# Dash22_LEDS.net
KiCad netlist of a schematic drawn in Altium Designer
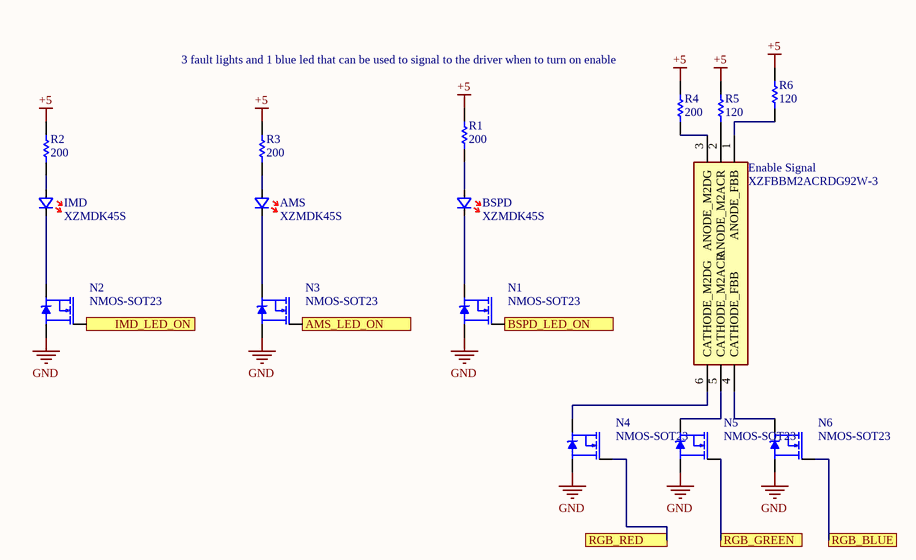
[diagram p0: Dash22_LEDS.SchDoc]

(export (version "E")
  (design (tool "Eeschema 10.0.6"))
  (components
    (comp (ref "AMS")
      (value "XZMDK45S")
      (footprint "LED_XZFBB45S")
      (fields (field (name "SOURCE") "ife19_Elec_Library.schlib"))
      (libsource (lib "Illini Formula Electric") (part "Symbol"))
    )
    (comp (ref "BSPD")
      (value "XZMDK45S")
      (footprint "LED_XZFBB45S")
      (fields (field (name "SOURCE") "ife19_Elec_Library.schlib"))
      (libsource (lib "Illini Formula Electric") (part "Symbol"))
    )
    (comp (ref "Enable Signal")
      (value "XZFBBM2ACRDG92W-3")
      (footprint "SamacSys:XZFBBM2ACRDG92W3")
      (description "LED")
      (libsource (lib "*") (part "XZFBBM2ACRDG92W-3"))
    )
    (comp (ref "IMD")
      (value "XZMDK45S")
      (footprint "LED_XZFBB45S")
      (fields (field (name "SOURCE") "ife19_Elec_Library.schlib"))
      (libsource (lib "Illini Formula Electric") (part "Symbol"))
    )
    (comp (ref "N1")
      (value "NMOS-SOT23")
      (footprint "SOT23")
      (fields (field (name "SOURCE") "ife19_Elec_Library.schlib"))
      (libsource (lib "Illini Formula Electric") (part "NMOS-SOT23"))
    )
    (comp (ref "N2")
      (value "NMOS-SOT23")
      (footprint "SOT23")
      (fields (field (name "SOURCE") "ife19_Elec_Library.schlib"))
      (libsource (lib "Illini Formula Electric") (part "NMOS-SOT23"))
    )
    (comp (ref "N3")
      (value "NMOS-SOT23")
      (footprint "SOT23")
      (fields (field (name "SOURCE") "ife19_Elec_Library.schlib"))
      (libsource (lib "Illini Formula Electric") (part "NMOS-SOT23"))
    )
    (comp (ref "N4")
      (value "NMOS-SOT23")
      (footprint "SOT23")
      (fields (field (name "SOURCE") "ife19_Elec_Library.schlib"))
      (libsource (lib "Illini Formula Electric") (part "NMOS-SOT23"))
    )
    (comp (ref "N5")
      (value "NMOS-SOT23")
      (footprint "SOT23")
      (fields (field (name "SOURCE") "ife19_Elec_Library.schlib"))
      (libsource (lib "Illini Formula Electric") (part "NMOS-SOT23"))
    )
    (comp (ref "N6")
      (value "NMOS-SOT23")
      (footprint "SOT23")
      (fields (field (name "SOURCE") "ife19_Elec_Library.schlib"))
      (libsource (lib "Illini Formula Electric") (part "NMOS-SOT23"))
    )
    (comp (ref "R1")
      (value "200")
      (footprint "RESC1608X55X25ML10T15")
      (description "Chip Resistor, 0 Ohm, 0.1 W, -55 to 155 degC, 0603 (1608 Metric)")
      (libsource (lib "") (part "Symbol_1"))
    )
    (comp (ref "R2")
      (value "200")
      (footprint "RESC1608X55X25ML10T15")
      (description "Chip Resistor, 0 Ohm, 0.1 W, -55 to 155 degC, 0603 (1608 Metric)")
      (libsource (lib "") (part "Symbol_1"))
    )
    (comp (ref "R3")
      (value "200")
      (footprint "RESC1608X55X25ML10T15")
      (description "Chip Resistor, 0 Ohm, 0.1 W, -55 to 155 degC, 0603 (1608 Metric)")
      (libsource (lib "") (part "Symbol_1"))
    )
    (comp (ref "R4")
      (value "200")
      (footprint "RESC1608X55X25ML10T15")
      (description "Chip Resistor, 0 Ohm, 0.1 W, -55 to 155 degC, 0603 (1608 Metric)")
      (libsource (lib "") (part "Symbol_1"))
    )
    (comp (ref "R5")
      (value "120")
      (footprint "RESC1608X55X25ML10T15")
      (description "Chip Resistor, 0 Ohm, 0.1 W, -55 to 155 degC, 0603 (1608 Metric)")
      (libsource (lib "") (part "Symbol_1"))
    )
    (comp (ref "R6")
      (value "120")
      (footprint "RESC1608X55X25ML10T15")
      (description "Chip Resistor, 0 Ohm, 0.1 W, -55 to 155 degC, 0603 (1608 Metric)")
      (libsource (lib "") (part "Symbol_1"))
    )
  )
  (nets
    (net (code "1") (name "+5") (class "Default")
      (node (ref "R1") (pin "2") (pinfunction "2_2") (pintype "passive"))
      (node (ref "R2") (pin "2") (pinfunction "2_2") (pintype "passive"))
      (node (ref "R3") (pin "2") (pinfunction "2_2") (pintype "passive"))
      (node (ref "R4") (pin "2") (pinfunction "2_2") (pintype "passive"))
      (node (ref "R5") (pin "2") (pinfunction "2_2") (pintype "passive"))
      (node (ref "R6") (pin "2") (pinfunction "2_2") (pintype "passive"))
    )
    (net (code "2") (name "/AMS_LED_ON") (class "Default")
      (node (ref "N3") (pin "1") (pinfunction "G_1") (pintype "passive"))
    )
    (net (code "3") (name "/BSPD_LED_ON") (class "Default")
      (node (ref "N1") (pin "1") (pinfunction "G_1") (pintype "passive"))
    )
    (net (code "4") (name "/IMD_LED_ON") (class "Default")
      (node (ref "N2") (pin "1") (pinfunction "G_1") (pintype "passive"))
    )
    (net (code "5") (name "/RGB_BLUE") (class "Default")
      (node (ref "N6") (pin "1") (pinfunction "G_1") (pintype "passive"))
    )
    (net (code "6") (name "/RGB_GREEN") (class "Default")
      (node (ref "N5") (pin "1") (pinfunction "G_1") (pintype "passive"))
    )
    (net (code "7") (name "/RGB_RED") (class "Default")
      (node (ref "N4") (pin "1") (pinfunction "G_1") (pintype "passive"))
    )
    (net (code "8") (name "GND") (class "Default")
      (node (ref "N1") (pin "2") (pinfunction "S_2") (pintype "passive"))
      (node (ref "N2") (pin "2") (pinfunction "S_2") (pintype "passive"))
      (node (ref "N3") (pin "2") (pinfunction "S_2") (pintype "passive"))
      (node (ref "N4") (pin "2") (pinfunction "S_2") (pintype "passive"))
      (node (ref "N5") (pin "2") (pinfunction "S_2") (pintype "passive"))
      (node (ref "N6") (pin "2") (pinfunction "S_2") (pintype "passive"))
    )
    (net (code "9") (name "Net-(AMS-PadA)") (class "Default")
      (node (ref "AMS") (pin "A") (pinfunction "A_A") (pintype "passive"))
      (node (ref "R3") (pin "1") (pinfunction "1_1") (pintype "passive"))
    )
    (net (code "10") (name "Net-(BSPD-PadA)") (class "Default")
      (node (ref "BSPD") (pin "A") (pinfunction "A_A") (pintype "passive"))
      (node (ref "R1") (pin "1") (pinfunction "1_1") (pintype "passive"))
    )
    (net (code "11") (name "Net-(Enable Signal-ANODE_FBB)") (class "Default")
      (node (ref "Enable Signal") (pin "1") (pinfunction "ANODE_FBB_1") (pintype "passive"))
      (node (ref "R6") (pin "1") (pinfunction "1_1") (pintype "passive"))
    )
    (net (code "12") (name "Net-(Enable Signal-ANODE_M2ACR)") (class "Default")
      (node (ref "Enable Signal") (pin "2") (pinfunction "ANODE_M2ACR_2") (pintype "passive"))
      (node (ref "R5") (pin "1") (pinfunction "1_1") (pintype "passive"))
    )
    (net (code "13") (name "Net-(Enable Signal-ANODE_M2DG)") (class "Default")
      (node (ref "Enable Signal") (pin "3") (pinfunction "ANODE_M2DG_3") (pintype "passive"))
      (node (ref "R4") (pin "1") (pinfunction "1_1") (pintype "passive"))
    )
    (net (code "14") (name "Net-(Enable Signal-CATHODE_FBB)") (class "Default")
      (node (ref "Enable Signal") (pin "4") (pinfunction "CATHODE_FBB_4") (pintype "passive"))
      (node (ref "N6") (pin "3") (pinfunction "D_3") (pintype "passive"))
    )
    (net (code "15") (name "Net-(Enable Signal-CATHODE_M2ACR)") (class "Default")
      (node (ref "Enable Signal") (pin "5") (pinfunction "CATHODE_M2ACR_5") (pintype "passive"))
      (node (ref "N5") (pin "3") (pinfunction "D_3") (pintype "passive"))
    )
    (net (code "16") (name "Net-(Enable Signal-CATHODE_M2DG)") (class "Default")
      (node (ref "Enable Signal") (pin "6") (pinfunction "CATHODE_M2DG_6") (pintype "passive"))
      (node (ref "N4") (pin "3") (pinfunction "D_3") (pintype "passive"))
    )
    (net (code "17") (name "Net-(IMD-PadA)") (class "Default")
      (node (ref "IMD") (pin "A") (pinfunction "A_A") (pintype "passive"))
      (node (ref "R2") (pin "1") (pinfunction "1_1") (pintype "passive"))
    )
    (net (code "18") (name "Net-(N1-D)") (class "Default")
      (node (ref "BSPD") (pin "K") (pinfunction "K_K") (pintype "passive"))
      (node (ref "N1") (pin "3") (pinfunction "D_3") (pintype "passive"))
    )
    (net (code "19") (name "Net-(N2-D)") (class "Default")
      (node (ref "IMD") (pin "K") (pinfunction "K_K") (pintype "passive"))
      (node (ref "N2") (pin "3") (pinfunction "D_3") (pintype "passive"))
    )
    (net (code "20") (name "Net-(N3-D)") (class "Default")
      (node (ref "AMS") (pin "K") (pinfunction "K_K") (pintype "passive"))
      (node (ref "N3") (pin "3") (pinfunction "D_3") (pintype "passive"))
    )
  )
)
